# DO.net
KiCad netlist of a schematic drawn in Altium Designer
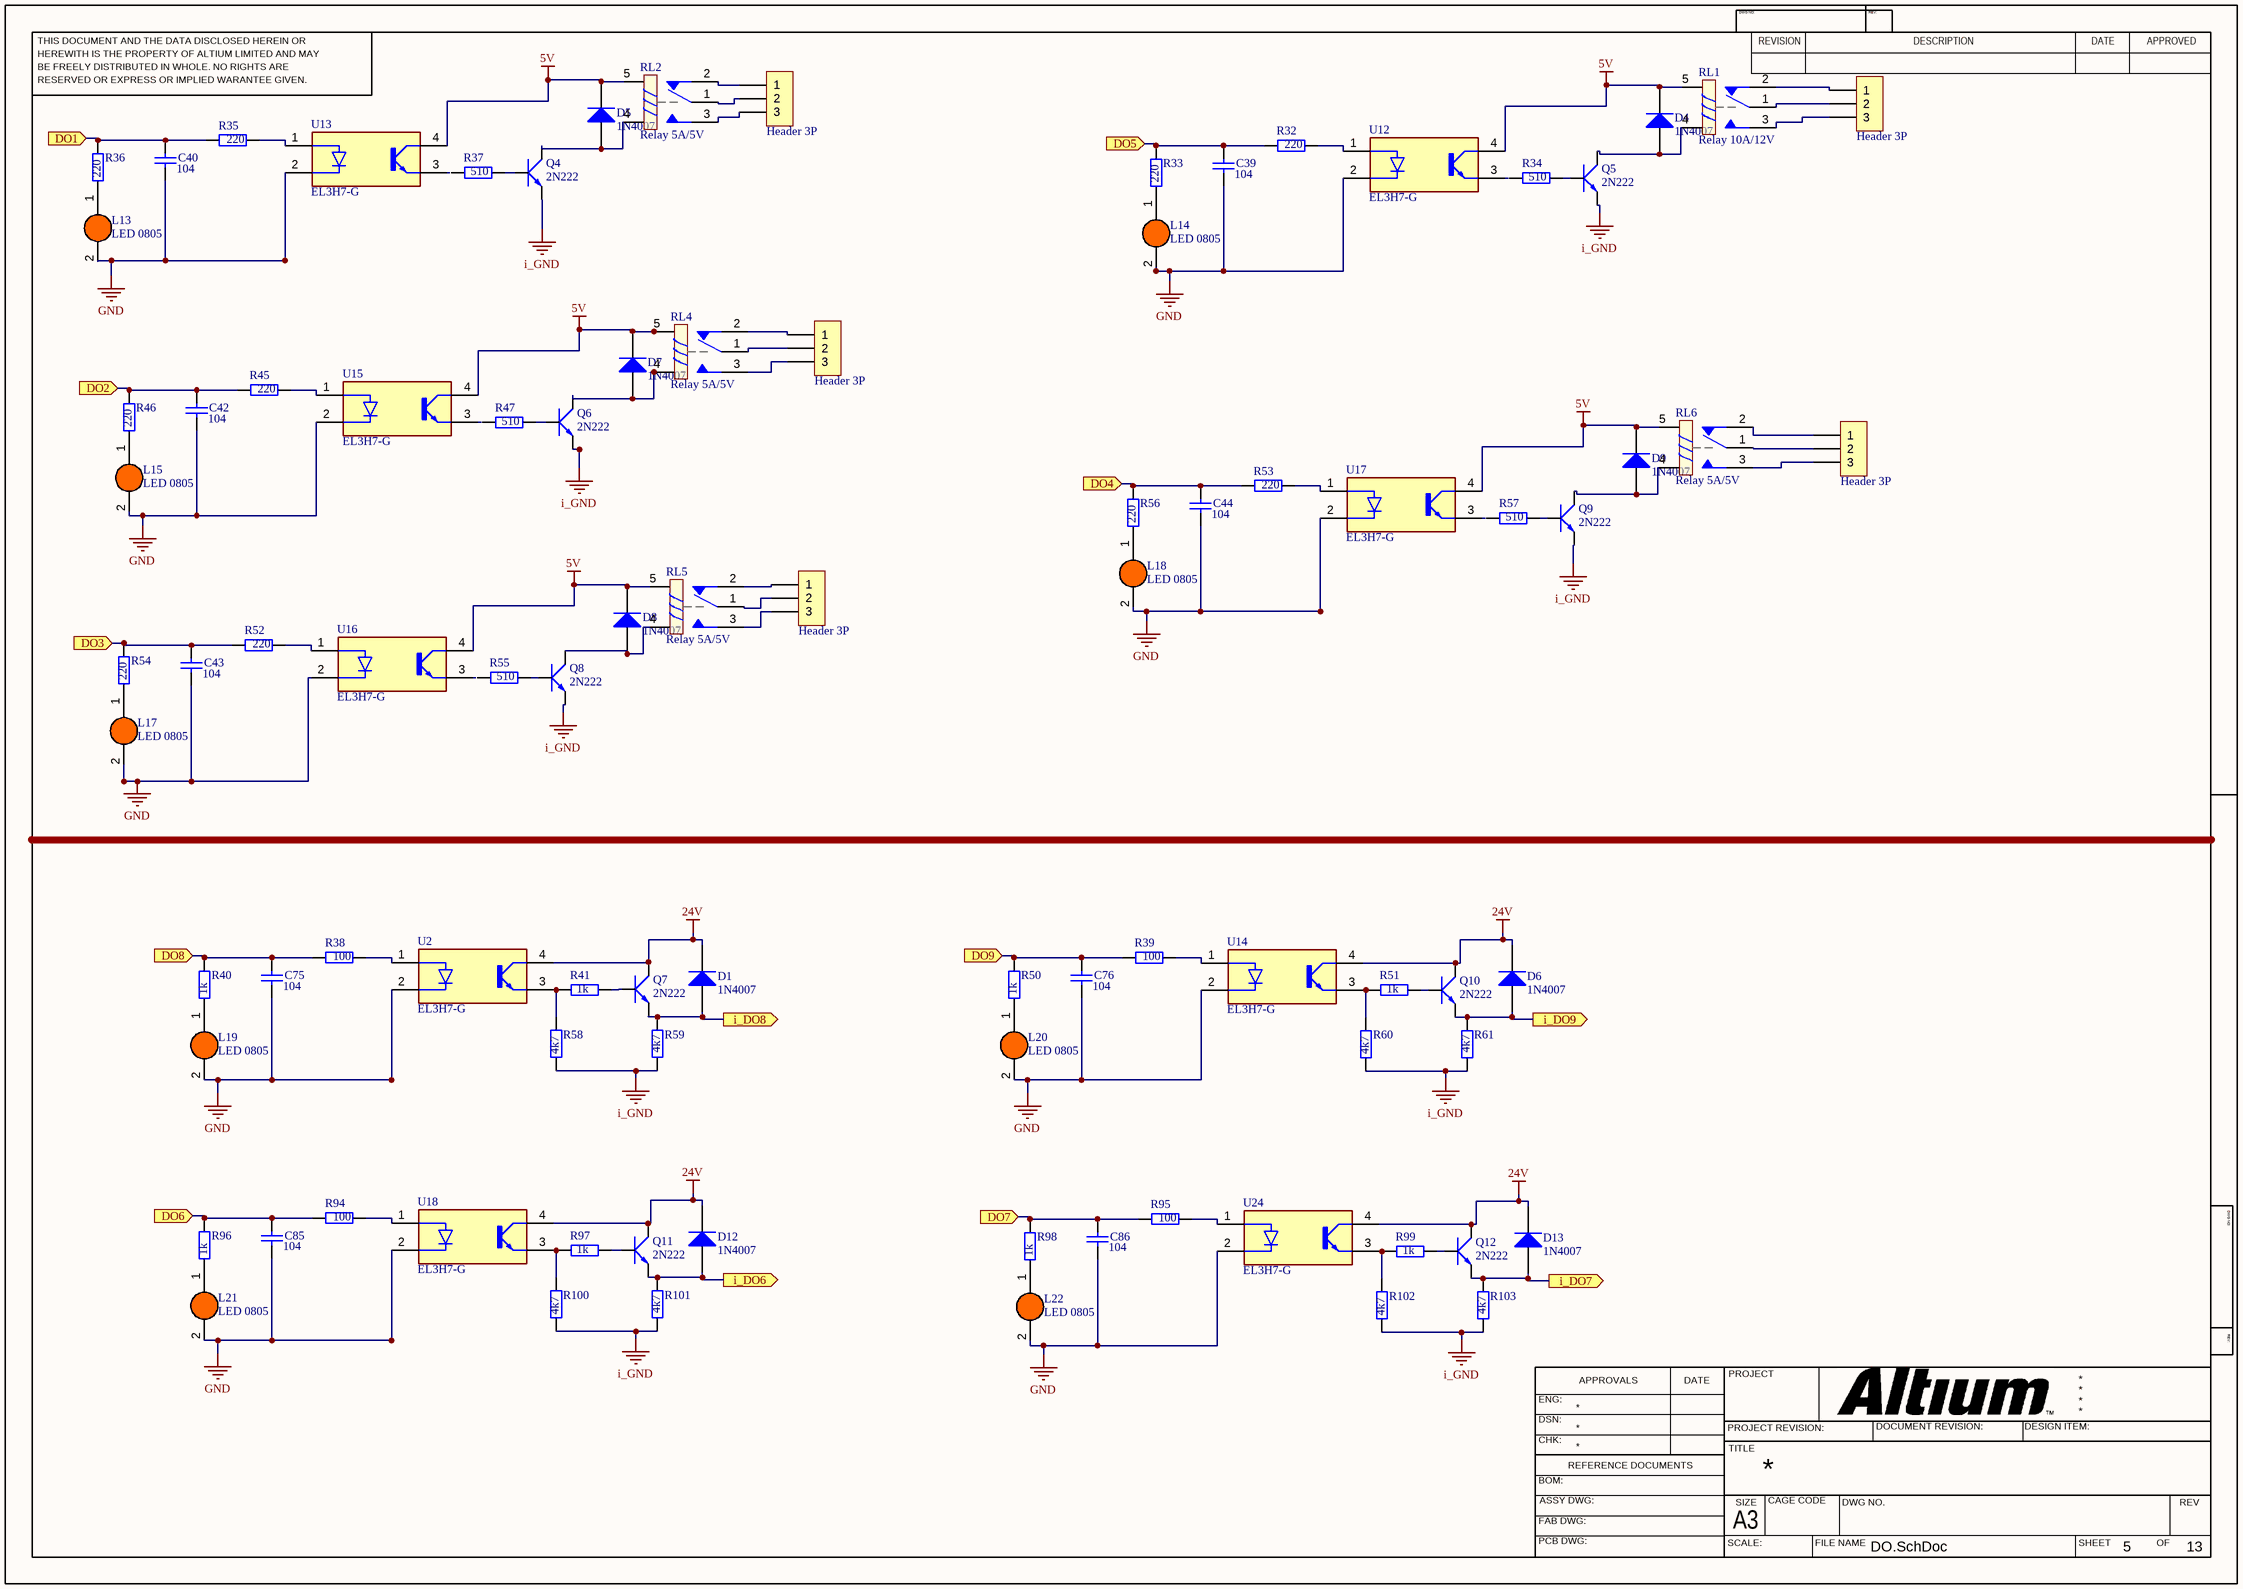
[diagram p0: DO.SchDoc]

(export (version "E")
  (design (tool "Eeschema 10.0.6"))
  (components
    (comp (ref "C39") (value "104") (footprint "0603_Cap") (libsource (lib "CMN") (part "Ceramic Capacitor")))
    (comp (ref "C40") (value "104") (footprint "0603_Cap") (libsource (lib "CMN") (part "Ceramic Capacitor")))
    (comp (ref "C42") (value "104") (footprint "0603_Cap") (libsource (lib "CMN") (part "Ceramic Capacitor")))
    (comp (ref "C43") (value "104") (footprint "0603_Cap") (libsource (lib "CMN") (part "Ceramic Capacitor")))
    (comp (ref "C44") (value "104") (footprint "0603_Cap") (libsource (lib "CMN") (part "Ceramic Capacitor")))
    (comp (ref "C75") (value "104") (footprint "0603_Cap") (libsource (lib "CMN") (part "Ceramic Capacitor")))
    (comp (ref "C76") (value "104") (footprint "0603_Cap") (libsource (lib "CMN") (part "Ceramic Capacitor")))
    (comp (ref "C85") (value "104") (footprint "0603_Cap") (libsource (lib "CMN") (part "Ceramic Capacitor")))
    (comp (ref "C86") (value "104") (footprint "0603_Cap") (libsource (lib "CMN") (part "Ceramic Capacitor")))
    (comp (ref "D1") (value "1N4007") (footprint "SMA - DO-214AC") (libsource (lib "CMN") (part "Diode")))
    (comp (ref "D4") (value "1N4007") (footprint "SMA - DO-214AC") (libsource (lib "CMN") (part "Diode")))
    (comp (ref "D5") (value "1N4007") (footprint "SMA - DO-214AC") (libsource (lib "CMN") (part "Diode")))
    (comp (ref "D6") (value "1N4007") (footprint "SMA - DO-214AC") (libsource (lib "CMN") (part "Diode")))
    (comp (ref "D7") (value "1N4007") (footprint "SMA - DO-214AC") (libsource (lib "CMN") (part "Diode")))
    (comp (ref "D8") (value "1N4007") (footprint "SMA - DO-214AC") (libsource (lib "CMN") (part "Diode")))
    (comp (ref "D9") (value "1N4007") (footprint "SMA - DO-214AC") (libsource (lib "CMN") (part "Diode")))
    (comp (ref "D12") (value "1N4007") (footprint "SMA - DO-214AC") (libsource (lib "CMN") (part "Diode")))
    (comp (ref "D13") (value "1N4007") (footprint "SMA - DO-214AC") (libsource (lib "CMN") (part "Diode")))
    (comp (ref "H17")
      (value "Header 3P")
      (footprint "CON 3 EDG5.08-3P")
      (description "THT")
      (libsource (lib "CMN") (part "Header 3P"))
    )
    (comp (ref "H18")
      (value "Header 3P")
      (footprint "CON 3 EDG5.08-3P")
      (description "THT")
      (libsource (lib "CMN") (part "Header 3P"))
    )
    (comp (ref "H20")
      (value "Header 3P")
      (footprint "CON 3 EDG5.08-3P")
      (description "THT")
      (libsource (lib "CMN") (part "Header 3P"))
    )
    (comp (ref "H21")
      (value "Header 3P")
      (footprint "CON 3 EDG5.08-3P")
      (description "THT")
      (libsource (lib "CMN") (part "Header 3P"))
    )
    (comp (ref "H22")
      (value "Header 3P")
      (footprint "CON 3 EDG5.08-3P")
      (description "THT")
      (libsource (lib "CMN") (part "Header 3P"))
    )
    (comp (ref "L13")
      (value "LED 0805")
      (footprint "LED-0805-Orange")
      (description "Dán")
      (libsource (lib "Led") (part "LED 0805 Cam"))
    )
    (comp (ref "L14")
      (value "LED 0805")
      (footprint "LED-0805-Orange")
      (description "Dán")
      (libsource (lib "Led") (part "LED 0805 Cam"))
    )
    (comp (ref "L15")
      (value "LED 0805")
      (footprint "LED-0805-Orange")
      (description "Dán")
      (libsource (lib "Led") (part "LED 0805 Cam"))
    )
    (comp (ref "L17")
      (value "LED 0805")
      (footprint "LED-0805-Orange")
      (description "Dán")
      (libsource (lib "Led") (part "LED 0805 Cam"))
    )
    (comp (ref "L18")
      (value "LED 0805")
      (footprint "LED-0805-Orange")
      (description "Dán")
      (libsource (lib "Led") (part "LED 0805 Cam"))
    )
    (comp (ref "L19")
      (value "LED 0805")
      (footprint "LED-0805-Orange")
      (description "Dán")
      (libsource (lib "Led") (part "LED 0805 Cam"))
    )
    (comp (ref "L20")
      (value "LED 0805")
      (footprint "LED-0805-Orange")
      (description "Dán")
      (libsource (lib "Led") (part "LED 0805 Cam"))
    )
    (comp (ref "L21")
      (value "LED 0805")
      (footprint "LED-0805-Orange")
      (description "Dán")
      (libsource (lib "Led") (part "LED 0805 Cam"))
    )
    (comp (ref "L22")
      (value "LED 0805")
      (footprint "LED-0805-Orange")
      (description "Dán")
      (libsource (lib "Led") (part "LED 0805 Cam"))
    )
    (comp (ref "Q4")
      (value "2N222")
      (footprint "SOT23-231")
      (description "NPN 600mW, ECB")
      (libsource (lib "KhanhBK_Library_4") (part "2N222"))
    )
    (comp (ref "Q5")
      (value "2N222")
      (footprint "SOT23-231")
      (description "NPN 600mW, ECB")
      (libsource (lib "KhanhBK_Library_4") (part "2N222"))
    )
    (comp (ref "Q6")
      (value "2N222")
      (footprint "SOT23-231")
      (description "NPN 600mW, ECB")
      (libsource (lib "KhanhBK_Library_4") (part "2N222"))
    )
    (comp (ref "Q7")
      (value "2N222")
      (footprint "SOT23-231")
      (description "NPN 600mW, ECB")
      (libsource (lib "KhanhBK_Library_4") (part "2N222"))
    )
    (comp (ref "Q8")
      (value "2N222")
      (footprint "SOT23-231")
      (description "NPN 600mW, ECB")
      (libsource (lib "KhanhBK_Library_4") (part "2N222"))
    )
    (comp (ref "Q9")
      (value "2N222")
      (footprint "SOT23-231")
      (description "NPN 600mW, ECB")
      (libsource (lib "KhanhBK_Library_4") (part "2N222"))
    )
    (comp (ref "Q10")
      (value "2N222")
      (footprint "SOT23-231")
      (description "NPN 600mW, ECB")
      (libsource (lib "KhanhBK_Library_4") (part "2N222"))
    )
    (comp (ref "Q11")
      (value "2N222")
      (footprint "SOT23-231")
      (description "NPN 600mW, ECB")
      (libsource (lib "KhanhBK_Library_4") (part "2N222"))
    )
    (comp (ref "Q12")
      (value "2N222")
      (footprint "SOT23-231")
      (description "NPN 600mW, ECB")
      (libsource (lib "KhanhBK_Library_4") (part "2N222"))
    )
    (comp (ref "R32") (value "220") (footprint "0603_Res") (libsource (lib "CMN") (part "Resistor")))
    (comp (ref "R33") (value "220") (footprint "0603_Res") (libsource (lib "CMN") (part "Resistor")))
    (comp (ref "R34") (value "510") (footprint "0603_Res") (libsource (lib "CMN") (part "Resistor")))
    (comp (ref "R35") (value "220") (footprint "0603_Res") (libsource (lib "CMN") (part "Resistor")))
    (comp (ref "R36") (value "220") (footprint "0603_Res") (libsource (lib "CMN") (part "Resistor")))
    (comp (ref "R37") (value "510") (footprint "0603_Res") (libsource (lib "CMN") (part "Resistor")))
    (comp (ref "R38") (value "100") (footprint "0603_Res") (libsource (lib "CMN") (part "Resistor")))
    (comp (ref "R39") (value "100") (footprint "0603_Res") (libsource (lib "CMN") (part "Resistor")))
    (comp (ref "R40") (value "1k") (footprint "0603_Res") (libsource (lib "CMN") (part "Resistor")))
    (comp (ref "R41") (value "1k") (footprint "0603_Res") (libsource (lib "CMN") (part "Resistor")))
    (comp (ref "R45") (value "220") (footprint "0603_Res") (libsource (lib "CMN") (part "Resistor")))
    (comp (ref "R46") (value "220") (footprint "0603_Res") (libsource (lib "CMN") (part "Resistor")))
    (comp (ref "R47") (value "510") (footprint "0603_Res") (libsource (lib "CMN") (part "Resistor")))
    (comp (ref "R50") (value "1k") (footprint "0603_Res") (libsource (lib "CMN") (part "Resistor")))
    (comp (ref "R51") (value "1k") (footprint "0603_Res") (libsource (lib "CMN") (part "Resistor")))
    (comp (ref "R52") (value "220") (footprint "0603_Res") (libsource (lib "CMN") (part "Resistor")))
    (comp (ref "R53") (value "220") (footprint "0603_Res") (libsource (lib "CMN") (part "Resistor")))
    (comp (ref "R54") (value "220") (footprint "0603_Res") (libsource (lib "CMN") (part "Resistor")))
    (comp (ref "R55") (value "510") (footprint "0603_Res") (libsource (lib "CMN") (part "Resistor")))
    (comp (ref "R56") (value "220") (footprint "0603_Res") (libsource (lib "CMN") (part "Resistor")))
    (comp (ref "R57") (value "510") (footprint "0603_Res") (libsource (lib "CMN") (part "Resistor")))
    (comp (ref "R58") (value "4k7") (footprint "0603_Res") (libsource (lib "CMN") (part "Resistor")))
    (comp (ref "R59") (value "4k7") (footprint "0603_Res") (libsource (lib "CMN") (part "Resistor")))
    (comp (ref "R60") (value "4k7") (footprint "0603_Res") (libsource (lib "CMN") (part "Resistor")))
    (comp (ref "R61") (value "4k7") (footprint "0603_Res") (libsource (lib "CMN") (part "Resistor")))
    (comp (ref "R94") (value "100") (footprint "0603_Res") (libsource (lib "CMN") (part "Resistor")))
    (comp (ref "R95") (value "100") (footprint "0603_Res") (libsource (lib "CMN") (part "Resistor")))
    (comp (ref "R96") (value "1k") (footprint "0603_Res") (libsource (lib "CMN") (part "Resistor")))
    (comp (ref "R97") (value "1k") (footprint "0603_Res") (libsource (lib "CMN") (part "Resistor")))
    (comp (ref "R98") (value "1k") (footprint "0603_Res") (libsource (lib "CMN") (part "Resistor")))
    (comp (ref "R99") (value "1k") (footprint "0603_Res") (libsource (lib "CMN") (part "Resistor")))
    (comp (ref "R100") (value "4k7") (footprint "0603_Res") (libsource (lib "CMN") (part "Resistor")))
    (comp (ref "R101") (value "4k7") (footprint "0603_Res") (libsource (lib "CMN") (part "Resistor")))
    (comp (ref "R102") (value "4k7") (footprint "0603_Res") (libsource (lib "CMN") (part "Resistor")))
    (comp (ref "R103") (value "4k7") (footprint "0603_Res") (libsource (lib "CMN") (part "Resistor")))
    (comp (ref "RL1")
      (value "Relay 10A/12V")
      (footprint "RL_SPDT_10A")
      (description "Relay SPDT,10A - 12VDC 5 Pin")
      (libsource (lib "KhanhBK_Library_4") (part "Relay 1"))
    )
    (comp (ref "RL2")
      (value "Relay 5A/5V")
      (footprint "RL_SPDT_10A")
      (description "Relay SPDT,10A - 12VDC 5 Pin")
      (libsource (lib "KhanhBK_Library_4") (part "Relay 1"))
    )
    (comp (ref "RL4")
      (value "Relay 5A/5V")
      (footprint "RL_SPDT_10A")
      (description "Relay SPDT,10A - 12VDC 5 Pin")
      (libsource (lib "KhanhBK_Library_4") (part "Relay 1"))
    )
    (comp (ref "RL5")
      (value "Relay 5A/5V")
      (footprint "RL_SPDT_10A")
      (description "Relay SPDT,10A - 12VDC 5 Pin")
      (libsource (lib "KhanhBK_Library_4") (part "Relay 1"))
    )
    (comp (ref "RL6")
      (value "Relay 5A/5V")
      (footprint "RL_SPDT_10A")
      (description "Relay SPDT,10A - 12VDC 5 Pin")
      (libsource (lib "KhanhBK_Library_4") (part "Relay 1"))
    )
    (comp (ref "U2")
      (value "EL3H7-G")
      (footprint "SSOP-4")
      (description "Optoisolator Transistor Output 3750Vrms 1 Channel 4-SSOP")
      (fields (field (name "MF") "Everlight Electronics"))
      (libsource (lib "CMN") (part "EL3H7-G"))
    )
    (comp (ref "U12")
      (value "EL3H7-G")
      (footprint "SSOP-4")
      (description "Optoisolator Transistor Output 3750Vrms 1 Channel 4-SSOP")
      (fields (field (name "MF") "Everlight Electronics"))
      (libsource (lib "CMN") (part "EL3H7-G"))
    )
    (comp (ref "U13")
      (value "EL3H7-G")
      (footprint "SSOP-4")
      (description "Optoisolator Transistor Output 3750Vrms 1 Channel 4-SSOP")
      (fields (field (name "MF") "Everlight Electronics"))
      (libsource (lib "CMN") (part "EL3H7-G"))
    )
    (comp (ref "U14")
      (value "EL3H7-G")
      (footprint "SSOP-4")
      (description "Optoisolator Transistor Output 3750Vrms 1 Channel 4-SSOP")
      (fields (field (name "MF") "Everlight Electronics"))
      (libsource (lib "CMN") (part "EL3H7-G"))
    )
    (comp (ref "U15")
      (value "EL3H7-G")
      (footprint "SSOP-4")
      (description "Optoisolator Transistor Output 3750Vrms 1 Channel 4-SSOP")
      (fields (field (name "MF") "Everlight Electronics"))
      (libsource (lib "CMN") (part "EL3H7-G"))
    )
    (comp (ref "U16")
      (value "EL3H7-G")
      (footprint "SSOP-4")
      (description "Optoisolator Transistor Output 3750Vrms 1 Channel 4-SSOP")
      (fields (field (name "MF") "Everlight Electronics"))
      (libsource (lib "CMN") (part "EL3H7-G"))
    )
    (comp (ref "U17")
      (value "EL3H7-G")
      (footprint "SSOP-4")
      (description "Optoisolator Transistor Output 3750Vrms 1 Channel 4-SSOP")
      (fields (field (name "MF") "Everlight Electronics"))
      (libsource (lib "CMN") (part "EL3H7-G"))
    )
    (comp (ref "U18")
      (value "EL3H7-G")
      (footprint "SSOP-4")
      (description "Optoisolator Transistor Output 3750Vrms 1 Channel 4-SSOP")
      (fields (field (name "MF") "Everlight Electronics"))
      (libsource (lib "CMN") (part "EL3H7-G"))
    )
    (comp (ref "U24")
      (value "EL3H7-G")
      (footprint "SSOP-4")
      (description "Optoisolator Transistor Output 3750Vrms 1 Channel 4-SSOP")
      (fields (field (name "MF") "Everlight Electronics"))
      (libsource (lib "CMN") (part "EL3H7-G"))
    )
  )
  (nets
    (net (code "1") (name "/DO1") (class "Default")
      (node (ref "C40") (pin "1") (pinfunction "1_1") (pintype "passive"))
      (node (ref "R35") (pin "1") (pinfunction "1_1") (pintype "passive"))
      (node (ref "R36") (pin "2") (pinfunction "2_2") (pintype "passive"))
    )
    (net (code "2") (name "/DO2") (class "Default")
      (node (ref "C42") (pin "1") (pinfunction "1_1") (pintype "passive"))
      (node (ref "R45") (pin "1") (pinfunction "1_1") (pintype "passive"))
      (node (ref "R46") (pin "2") (pinfunction "2_2") (pintype "passive"))
    )
    (net (code "3") (name "/DO3") (class "Default")
      (node (ref "C43") (pin "1") (pinfunction "1_1") (pintype "passive"))
      (node (ref "R52") (pin "1") (pinfunction "1_1") (pintype "passive"))
      (node (ref "R54") (pin "2") (pinfunction "2_2") (pintype "passive"))
    )
    (net (code "4") (name "/DO4") (class "Default")
      (node (ref "C44") (pin "1") (pinfunction "1_1") (pintype "passive"))
      (node (ref "R53") (pin "1") (pinfunction "1_1") (pintype "passive"))
      (node (ref "R56") (pin "2") (pinfunction "2_2") (pintype "passive"))
    )
    (net (code "5") (name "/DO5") (class "Default")
      (node (ref "C39") (pin "1") (pinfunction "1_1") (pintype "passive"))
      (node (ref "R32") (pin "1") (pinfunction "1_1") (pintype "passive"))
      (node (ref "R33") (pin "2") (pinfunction "2_2") (pintype "passive"))
    )
    (net (code "6") (name "/DO6") (class "Default")
      (node (ref "C85") (pin "1") (pinfunction "1_1") (pintype "passive"))
      (node (ref "R94") (pin "1") (pinfunction "1_1") (pintype "passive"))
      (node (ref "R96") (pin "2") (pinfunction "2_2") (pintype "passive"))
    )
    (net (code "7") (name "/DO7") (class "Default")
      (node (ref "C86") (pin "1") (pinfunction "1_1") (pintype "passive"))
      (node (ref "R95") (pin "1") (pinfunction "1_1") (pintype "passive"))
      (node (ref "R98") (pin "2") (pinfunction "2_2") (pintype "passive"))
    )
    (net (code "8") (name "/DO8") (class "Default")
      (node (ref "C75") (pin "1") (pinfunction "1_1") (pintype "passive"))
      (node (ref "R38") (pin "1") (pinfunction "1_1") (pintype "passive"))
      (node (ref "R40") (pin "2") (pinfunction "2_2") (pintype "passive"))
    )
    (net (code "9") (name "/DO9") (class "Default")
      (node (ref "C76") (pin "1") (pinfunction "1_1") (pintype "passive"))
      (node (ref "R39") (pin "1") (pinfunction "1_1") (pintype "passive"))
      (node (ref "R50") (pin "2") (pinfunction "2_2") (pintype "passive"))
    )
    (net (code "10") (name "/i_DO6") (class "Default")
      (node (ref "D12") (pin "2") (pinfunction "2_2") (pintype "passive"))
      (node (ref "Q11") (pin "1") (pinfunction "E_1") (pintype "passive"))
      (node (ref "R101") (pin "2") (pinfunction "2_2") (pintype "passive"))
    )
    (net (code "11") (name "/i_DO7") (class "Default")
      (node (ref "D13") (pin "2") (pinfunction "2_2") (pintype "passive"))
      (node (ref "Q12") (pin "1") (pinfunction "E_1") (pintype "passive"))
      (node (ref "R103") (pin "2") (pinfunction "2_2") (pintype "passive"))
    )
    (net (code "12") (name "/i_DO8") (class "Default")
      (node (ref "D1") (pin "2") (pinfunction "2_2") (pintype "passive"))
      (node (ref "Q7") (pin "1") (pinfunction "E_1") (pintype "passive"))
      (node (ref "R59") (pin "2") (pinfunction "2_2") (pintype "passive"))
    )
    (net (code "13") (name "/i_DO9") (class "Default")
      (node (ref "D6") (pin "2") (pinfunction "2_2") (pintype "passive"))
      (node (ref "Q10") (pin "1") (pinfunction "E_1") (pintype "passive"))
      (node (ref "R61") (pin "2") (pinfunction "2_2") (pintype "passive"))
    )
    (net (code "14") (name "5V") (class "Default")
      (node (ref "D4") (pin "1") (pinfunction "1_1") (pintype "passive"))
      (node (ref "D5") (pin "1") (pinfunction "1_1") (pintype "passive"))
      (node (ref "D7") (pin "1") (pinfunction "1_1") (pintype "passive"))
      (node (ref "D8") (pin "1") (pinfunction "1_1") (pintype "passive"))
      (node (ref "D9") (pin "1") (pinfunction "1_1") (pintype "passive"))
      (node (ref "RL1") (pin "5") (pinfunction "5_5") (pintype "passive"))
      (node (ref "RL2") (pin "5") (pinfunction "5_5") (pintype "passive"))
      (node (ref "RL4") (pin "5") (pinfunction "5_5") (pintype "passive"))
      (node (ref "RL5") (pin "5") (pinfunction "5_5") (pintype "passive"))
      (node (ref "RL6") (pin "5") (pinfunction "5_5") (pintype "passive"))
      (node (ref "U12") (pin "4") (pinfunction "CO_4") (pintype "passive"))
      (node (ref "U13") (pin "4") (pinfunction "CO_4") (pintype "passive"))
      (node (ref "U15") (pin "4") (pinfunction "CO_4") (pintype "passive"))
      (node (ref "U16") (pin "4") (pinfunction "CO_4") (pintype "passive"))
      (node (ref "U17") (pin "4") (pinfunction "CO_4") (pintype "passive"))
    )
    (net (code "15") (name "24V") (class "Default")
      (node (ref "D1") (pin "1") (pinfunction "1_1") (pintype "passive"))
      (node (ref "D12") (pin "1") (pinfunction "1_1") (pintype "passive"))
      (node (ref "D13") (pin "1") (pinfunction "1_1") (pintype "passive"))
      (node (ref "D6") (pin "1") (pinfunction "1_1") (pintype "passive"))
      (node (ref "Q10") (pin "3") (pinfunction "C_3") (pintype "passive"))
      (node (ref "Q11") (pin "3") (pinfunction "C_3") (pintype "passive"))
      (node (ref "Q12") (pin "3") (pinfunction "C_3") (pintype "passive"))
      (node (ref "Q7") (pin "3") (pinfunction "C_3") (pintype "passive"))
      (node (ref "U14") (pin "4") (pinfunction "CO_4") (pintype "passive"))
      (node (ref "U18") (pin "4") (pinfunction "CO_4") (pintype "passive"))
      (node (ref "U2") (pin "4") (pinfunction "CO_4") (pintype "passive"))
      (node (ref "U24") (pin "4") (pinfunction "CO_4") (pintype "passive"))
    )
    (net (code "16") (name "GND") (class "Default")
      (node (ref "C39") (pin "2") (pinfunction "2_2") (pintype "passive"))
      (node (ref "C40") (pin "2") (pinfunction "2_2") (pintype "passive"))
      (node (ref "C42") (pin "2") (pinfunction "2_2") (pintype "passive"))
      (node (ref "C43") (pin "2") (pinfunction "2_2") (pintype "passive"))
      (node (ref "C44") (pin "2") (pinfunction "2_2") (pintype "passive"))
      (node (ref "C75") (pin "2") (pinfunction "2_2") (pintype "passive"))
      (node (ref "C76") (pin "2") (pinfunction "2_2") (pintype "passive"))
      (node (ref "C85") (pin "2") (pinfunction "2_2") (pintype "passive"))
      (node (ref "C86") (pin "2") (pinfunction "2_2") (pintype "passive"))
      (node (ref "L13") (pin "2") (pinfunction "K_2") (pintype "passive"))
      (node (ref "L14") (pin "2") (pinfunction "K_2") (pintype "passive"))
      (node (ref "L15") (pin "2") (pinfunction "K_2") (pintype "passive"))
      (node (ref "L17") (pin "2") (pinfunction "K_2") (pintype "passive"))
      (node (ref "L18") (pin "2") (pinfunction "K_2") (pintype "passive"))
      (node (ref "L19") (pin "2") (pinfunction "K_2") (pintype "passive"))
      (node (ref "L20") (pin "2") (pinfunction "K_2") (pintype "passive"))
      (node (ref "L21") (pin "2") (pinfunction "K_2") (pintype "passive"))
      (node (ref "L22") (pin "2") (pinfunction "K_2") (pintype "passive"))
      (node (ref "U12") (pin "2") (pinfunction "C_2") (pintype "passive"))
      (node (ref "U13") (pin "2") (pinfunction "C_2") (pintype "passive"))
      (node (ref "U14") (pin "2") (pinfunction "C_2") (pintype "passive"))
      (node (ref "U15") (pin "2") (pinfunction "C_2") (pintype "passive"))
      (node (ref "U16") (pin "2") (pinfunction "C_2") (pintype "passive"))
      (node (ref "U17") (pin "2") (pinfunction "C_2") (pintype "passive"))
      (node (ref "U18") (pin "2") (pinfunction "C_2") (pintype "passive"))
      (node (ref "U2") (pin "2") (pinfunction "C_2") (pintype "passive"))
      (node (ref "U24") (pin "2") (pinfunction "C_2") (pintype "passive"))
    )
    (net (code "17") (name "Net-(H17-Pad1)") (class "Default")
      (node (ref "H17") (pin "1") (pinfunction "1_1") (pintype "passive"))
      (node (ref "RL1") (pin "2") (pinfunction "2_2") (pintype "passive"))
    )
    (net (code "18") (name "Net-(H17-Pad2)") (class "Default")
      (node (ref "H17") (pin "2") (pinfunction "2_2") (pintype "passive"))
      (node (ref "RL1") (pin "1") (pinfunction "1_1") (pintype "passive"))
    )
    (net (code "19") (name "Net-(H17-Pad3)") (class "Default")
      (node (ref "H17") (pin "3") (pinfunction "3_3") (pintype "passive"))
      (node (ref "RL1") (pin "3") (pinfunction "3_3") (pintype "passive"))
    )
    (net (code "20") (name "Net-(H18-Pad1)") (class "Default")
      (node (ref "H18") (pin "1") (pinfunction "1_1") (pintype "passive"))
      (node (ref "RL2") (pin "2") (pinfunction "2_2") (pintype "passive"))
    )
    (net (code "21") (name "Net-(H18-Pad2)") (class "Default")
      (node (ref "H18") (pin "2") (pinfunction "2_2") (pintype "passive"))
      (node (ref "RL2") (pin "1") (pinfunction "1_1") (pintype "passive"))
    )
    (net (code "22") (name "Net-(H18-Pad3)") (class "Default")
      (node (ref "H18") (pin "3") (pinfunction "3_3") (pintype "passive"))
      (node (ref "RL2") (pin "3") (pinfunction "3_3") (pintype "passive"))
    )
    (net (code "23") (name "Net-(H20-Pad1)") (class "Default")
      (node (ref "H20") (pin "1") (pinfunction "1_1") (pintype "passive"))
      (node (ref "RL4") (pin "2") (pinfunction "2_2") (pintype "passive"))
    )
    (net (code "24") (name "Net-(H20-Pad2)") (class "Default")
      (node (ref "H20") (pin "2") (pinfunction "2_2") (pintype "passive"))
      (node (ref "RL4") (pin "1") (pinfunction "1_1") (pintype "passive"))
    )
    (net (code "25") (name "Net-(H20-Pad3)") (class "Default")
      (node (ref "H20") (pin "3") (pinfunction "3_3") (pintype "passive"))
      (node (ref "RL4") (pin "3") (pinfunction "3_3") (pintype "passive"))
    )
    (net (code "26") (name "Net-(H21-Pad1)") (class "Default")
      (node (ref "H21") (pin "1") (pinfunction "1_1") (pintype "passive"))
      (node (ref "RL5") (pin "2") (pinfunction "2_2") (pintype "passive"))
    )
    (net (code "27") (name "Net-(H21-Pad2)") (class "Default")
      (node (ref "H21") (pin "2") (pinfunction "2_2") (pintype "passive"))
      (node (ref "RL5") (pin "1") (pinfunction "1_1") (pintype "passive"))
    )
    (net (code "28") (name "Net-(H21-Pad3)") (class "Default")
      (node (ref "H21") (pin "3") (pinfunction "3_3") (pintype "passive"))
      (node (ref "RL5") (pin "3") (pinfunction "3_3") (pintype "passive"))
    )
    (net (code "29") (name "Net-(H22-Pad1)") (class "Default")
      (node (ref "H22") (pin "1") (pinfunction "1_1") (pintype "passive"))
      (node (ref "RL6") (pin "2") (pinfunction "2_2") (pintype "passive"))
    )
    (net (code "30") (name "Net-(H22-Pad2)") (class "Default")
      (node (ref "H22") (pin "2") (pinfunction "2_2") (pintype "passive"))
      (node (ref "RL6") (pin "1") (pinfunction "1_1") (pintype "passive"))
    )
    (net (code "31") (name "Net-(H22-Pad3)") (class "Default")
      (node (ref "H22") (pin "3") (pinfunction "3_3") (pintype "passive"))
      (node (ref "RL6") (pin "3") (pinfunction "3_3") (pintype "passive"))
    )
    (net (code "32") (name "Net-(L13-A)") (class "Default")
      (node (ref "L13") (pin "1") (pinfunction "A_1") (pintype "passive"))
      (node (ref "R36") (pin "1") (pinfunction "1_1") (pintype "passive"))
    )
    (net (code "33") (name "Net-(L14-A)") (class "Default")
      (node (ref "L14") (pin "1") (pinfunction "A_1") (pintype "passive"))
      (node (ref "R33") (pin "1") (pinfunction "1_1") (pintype "passive"))
    )
    (net (code "34") (name "Net-(L15-A)") (class "Default")
      (node (ref "L15") (pin "1") (pinfunction "A_1") (pintype "passive"))
      (node (ref "R46") (pin "1") (pinfunction "1_1") (pintype "passive"))
    )
    (net (code "35") (name "Net-(L17-A)") (class "Default")
      (node (ref "L17") (pin "1") (pinfunction "A_1") (pintype "passive"))
      (node (ref "R54") (pin "1") (pinfunction "1_1") (pintype "passive"))
    )
    (net (code "36") (name "Net-(L18-A)") (class "Default")
      (node (ref "L18") (pin "1") (pinfunction "A_1") (pintype "passive"))
      (node (ref "R56") (pin "1") (pinfunction "1_1") (pintype "passive"))
    )
    (net (code "37") (name "Net-(L19-A)") (class "Default")
      (node (ref "L19") (pin "1") (pinfunction "A_1") (pintype "passive"))
      (node (ref "R40") (pin "1") (pinfunction "1_1") (pintype "passive"))
    )
    (net (code "38") (name "Net-(L20-A)") (class "Default")
      (node (ref "L20") (pin "1") (pinfunction "A_1") (pintype "passive"))
      (node (ref "R50") (pin "1") (pinfunction "1_1") (pintype "passive"))
    )
    (net (code "39") (name "Net-(L21-A)") (class "Default")
      (node (ref "L21") (pin "1") (pinfunction "A_1") (pintype "passive"))
      (node (ref "R96") (pin "1") (pinfunction "1_1") (pintype "passive"))
    )
    (net (code "40") (name "Net-(L22-A)") (class "Default")
      (node (ref "L22") (pin "1") (pinfunction "A_1") (pintype "passive"))
      (node (ref "R98") (pin "1") (pinfunction "1_1") (pintype "passive"))
    )
    (net (code "41") (name "Net-(Q4-B)") (class "Default")
      (node (ref "Q4") (pin "2") (pinfunction "B_2") (pintype "passive"))
      (node (ref "R37") (pin "2") (pinfunction "2_2") (pintype "passive"))
    )
    (net (code "42") (name "Net-(Q4-C)") (class "Default")
      (node (ref "D5") (pin "2") (pinfunction "2_2") (pintype "passive"))
      (node (ref "Q4") (pin "3") (pinfunction "C_3") (pintype "passive"))
      (node (ref "RL2") (pin "4") (pinfunction "4_4") (pintype "passive"))
    )
    (net (code "43") (name "Net-(Q5-B)") (class "Default")
      (node (ref "Q5") (pin "2") (pinfunction "B_2") (pintype "passive"))
      (node (ref "R34") (pin "2") (pinfunction "2_2") (pintype "passive"))
    )
    (net (code "44") (name "Net-(Q5-C)") (class "Default")
      (node (ref "D4") (pin "2") (pinfunction "2_2") (pintype "passive"))
      (node (ref "Q5") (pin "3") (pinfunction "C_3") (pintype "passive"))
      (node (ref "RL1") (pin "4") (pinfunction "4_4") (pintype "passive"))
    )
    (net (code "45") (name "Net-(Q6-B)") (class "Default")
      (node (ref "Q6") (pin "2") (pinfunction "B_2") (pintype "passive"))
      (node (ref "R47") (pin "2") (pinfunction "2_2") (pintype "passive"))
    )
    (net (code "46") (name "Net-(Q6-C)") (class "Default")
      (node (ref "D7") (pin "2") (pinfunction "2_2") (pintype "passive"))
      (node (ref "Q6") (pin "3") (pinfunction "C_3") (pintype "passive"))
      (node (ref "RL4") (pin "4") (pinfunction "4_4") (pintype "passive"))
    )
    (net (code "47") (name "Net-(Q7-B)") (class "Default")
      (node (ref "Q7") (pin "2") (pinfunction "B_2") (pintype "passive"))
      (node (ref "R41") (pin "2") (pinfunction "2_2") (pintype "passive"))
    )
    (net (code "48") (name "Net-(Q8-B)") (class "Default")
      (node (ref "Q8") (pin "2") (pinfunction "B_2") (pintype "passive"))
      (node (ref "R55") (pin "2") (pinfunction "2_2") (pintype "passive"))
    )
    (net (code "49") (name "Net-(Q8-C)") (class "Default")
      (node (ref "D8") (pin "2") (pinfunction "2_2") (pintype "passive"))
      (node (ref "Q8") (pin "3") (pinfunction "C_3") (pintype "passive"))
      (node (ref "RL5") (pin "4") (pinfunction "4_4") (pintype "passive"))
    )
    (net (code "50") (name "Net-(Q9-B)") (class "Default")
      (node (ref "Q9") (pin "2") (pinfunction "B_2") (pintype "passive"))
      (node (ref "R57") (pin "2") (pinfunction "2_2") (pintype "passive"))
    )
    (net (code "51") (name "Net-(Q9-C)") (class "Default")
      (node (ref "D9") (pin "2") (pinfunction "2_2") (pintype "passive"))
      (node (ref "Q9") (pin "3") (pinfunction "C_3") (pintype "passive"))
      (node (ref "RL6") (pin "4") (pinfunction "4_4") (pintype "passive"))
    )
    (net (code "52") (name "Net-(Q10-B)") (class "Default")
      (node (ref "Q10") (pin "2") (pinfunction "B_2") (pintype "passive"))
      (node (ref "R51") (pin "2") (pinfunction "2_2") (pintype "passive"))
    )
    (net (code "53") (name "Net-(Q11-B)") (class "Default")
      (node (ref "Q11") (pin "2") (pinfunction "B_2") (pintype "passive"))
      (node (ref "R97") (pin "2") (pinfunction "2_2") (pintype "passive"))
    )
    (net (code "54") (name "Net-(Q12-B)") (class "Default")
      (node (ref "Q12") (pin "2") (pinfunction "B_2") (pintype "passive"))
      (node (ref "R99") (pin "2") (pinfunction "2_2") (pintype "passive"))
    )
    (net (code "55") (name "Net-(U2-A)") (class "Default")
      (node (ref "R38") (pin "2") (pinfunction "2_2") (pintype "passive"))
      (node (ref "U2") (pin "1") (pinfunction "A_1") (pintype "passive"))
    )
    (net (code "56") (name "Net-(U2-E)") (class "Default")
      (node (ref "R41") (pin "1") (pinfunction "1_1") (pintype "passive"))
      (node (ref "R58") (pin "2") (pinfunction "2_2") (pintype "passive"))
      (node (ref "U2") (pin "3") (pinfunction "E_3") (pintype "passive"))
    )
    (net (code "57") (name "Net-(U12-A)") (class "Default")
      (node (ref "R32") (pin "2") (pinfunction "2_2") (pintype "passive"))
      (node (ref "U12") (pin "1") (pinfunction "A_1") (pintype "passive"))
    )
    (net (code "58") (name "Net-(U13-A)") (class "Default")
      (node (ref "R35") (pin "2") (pinfunction "2_2") (pintype "passive"))
      (node (ref "U13") (pin "1") (pinfunction "A_1") (pintype "passive"))
    )
    (net (code "59") (name "Net-(U14-A)") (class "Default")
      (node (ref "R39") (pin "2") (pinfunction "2_2") (pintype "passive"))
      (node (ref "U14") (pin "1") (pinfunction "A_1") (pintype "passive"))
    )
    (net (code "60") (name "Net-(U14-E)") (class "Default")
      (node (ref "R51") (pin "1") (pinfunction "1_1") (pintype "passive"))
      (node (ref "R60") (pin "2") (pinfunction "2_2") (pintype "passive"))
      (node (ref "U14") (pin "3") (pinfunction "E_3") (pintype "passive"))
    )
    (net (code "61") (name "Net-(U15-A)") (class "Default")
      (node (ref "R45") (pin "2") (pinfunction "2_2") (pintype "passive"))
      (node (ref "U15") (pin "1") (pinfunction "A_1") (pintype "passive"))
    )
    (net (code "62") (name "Net-(U16-A)") (class "Default")
      (node (ref "R52") (pin "2") (pinfunction "2_2") (pintype "passive"))
      (node (ref "U16") (pin "1") (pinfunction "A_1") (pintype "passive"))
    )
    (net (code "63") (name "Net-(U17-A)") (class "Default")
      (node (ref "R53") (pin "2") (pinfunction "2_2") (pintype "passive"))
      (node (ref "U17") (pin "1") (pinfunction "A_1") (pintype "passive"))
    )
    (net (code "64") (name "Net-(U18-A)") (class "Default")
      (node (ref "R94") (pin "2") (pinfunction "2_2") (pintype "passive"))
      (node (ref "U18") (pin "1") (pinfunction "A_1") (pintype "passive"))
    )
    (net (code "65") (name "Net-(U18-E)") (class "Default")
      (node (ref "R100") (pin "2") (pinfunction "2_2") (pintype "passive"))
      (node (ref "R97") (pin "1") (pinfunction "1_1") (pintype "passive"))
      (node (ref "U18") (pin "3") (pinfunction "E_3") (pintype "passive"))
    )
    (net (code "66") (name "Net-(U24-A)") (class "Default")
      (node (ref "R95") (pin "2") (pinfunction "2_2") (pintype "passive"))
      (node (ref "U24") (pin "1") (pinfunction "A_1") (pintype "passive"))
    )
    (net (code "67") (name "Net-(U24-E)") (class "Default")
      (node (ref "R102") (pin "2") (pinfunction "2_2") (pintype "passive"))
      (node (ref "R99") (pin "1") (pinfunction "1_1") (pintype "passive"))
      (node (ref "U24") (pin "3") (pinfunction "E_3") (pintype "passive"))
    )
    (net (code "68") (name "i_GND") (class "Default")
      (node (ref "Q4") (pin "1") (pinfunction "E_1") (pintype "passive"))
      (node (ref "Q5") (pin "1") (pinfunction "E_1") (pintype "passive"))
      (node (ref "Q6") (pin "1") (pinfunction "E_1") (pintype "passive"))
      (node (ref "Q8") (pin "1") (pinfunction "E_1") (pintype "passive"))
      (node (ref "Q9") (pin "1") (pinfunction "E_1") (pintype "passive"))
      (node (ref "R100") (pin "1") (pinfunction "1_1") (pintype "passive"))
      (node (ref "R101") (pin "1") (pinfunction "1_1") (pintype "passive"))
      (node (ref "R102") (pin "1") (pinfunction "1_1") (pintype "passive"))
      (node (ref "R103") (pin "1") (pinfunction "1_1") (pintype "passive"))
      (node (ref "R58") (pin "1") (pinfunction "1_1") (pintype "passive"))
      (node (ref "R59") (pin "1") (pinfunction "1_1") (pintype "passive"))
      (node (ref "R60") (pin "1") (pinfunction "1_1") (pintype "passive"))
      (node (ref "R61") (pin "1") (pinfunction "1_1") (pintype "passive"))
    )
    (net (code "69") (name "unconnected-(R34-Pad1)") (class "Default")
      (node (ref "R34") (pin "1") (pinfunction "1_1") (pintype "passive"))
    )
    (net (code "70") (name "unconnected-(R37-Pad1)") (class "Default")
      (node (ref "R37") (pin "1") (pinfunction "1_1") (pintype "passive"))
    )
    (net (code "71") (name "unconnected-(R47-Pad1)") (class "Default")
      (node (ref "R47") (pin "1") (pinfunction "1_1") (pintype "passive"))
    )
    (net (code "72") (name "unconnected-(R55-Pad1)") (class "Default")
      (node (ref "R55") (pin "1") (pinfunction "1_1") (pintype "passive"))
    )
    (net (code "73") (name "unconnected-(R57-Pad1)") (class "Default")
      (node (ref "R57") (pin "1") (pinfunction "1_1") (pintype "passive"))
    )
    (net (code "74") (name "unconnected-(U12-E-Pad3)") (class "Default")
      (node (ref "U12") (pin "3") (pinfunction "E_3") (pintype "passive"))
    )
    (net (code "75") (name "unconnected-(U13-E-Pad3)") (class "Default")
      (node (ref "U13") (pin "3") (pinfunction "E_3") (pintype "passive"))
    )
    (net (code "76") (name "unconnected-(U15-E-Pad3)") (class "Default")
      (node (ref "U15") (pin "3") (pinfunction "E_3") (pintype "passive"))
    )
    (net (code "77") (name "unconnected-(U16-E-Pad3)") (class "Default")
      (node (ref "U16") (pin "3") (pinfunction "E_3") (pintype "passive"))
    )
    (net (code "78") (name "unconnected-(U17-E-Pad3)") (class "Default")
      (node (ref "U17") (pin "3") (pinfunction "E_3") (pintype "passive"))
    )
  )
)
